# Adapter_-_Cabled_2_wire_CRXB4M.net
KiCad netlist of a schematic drawn in EAGLE
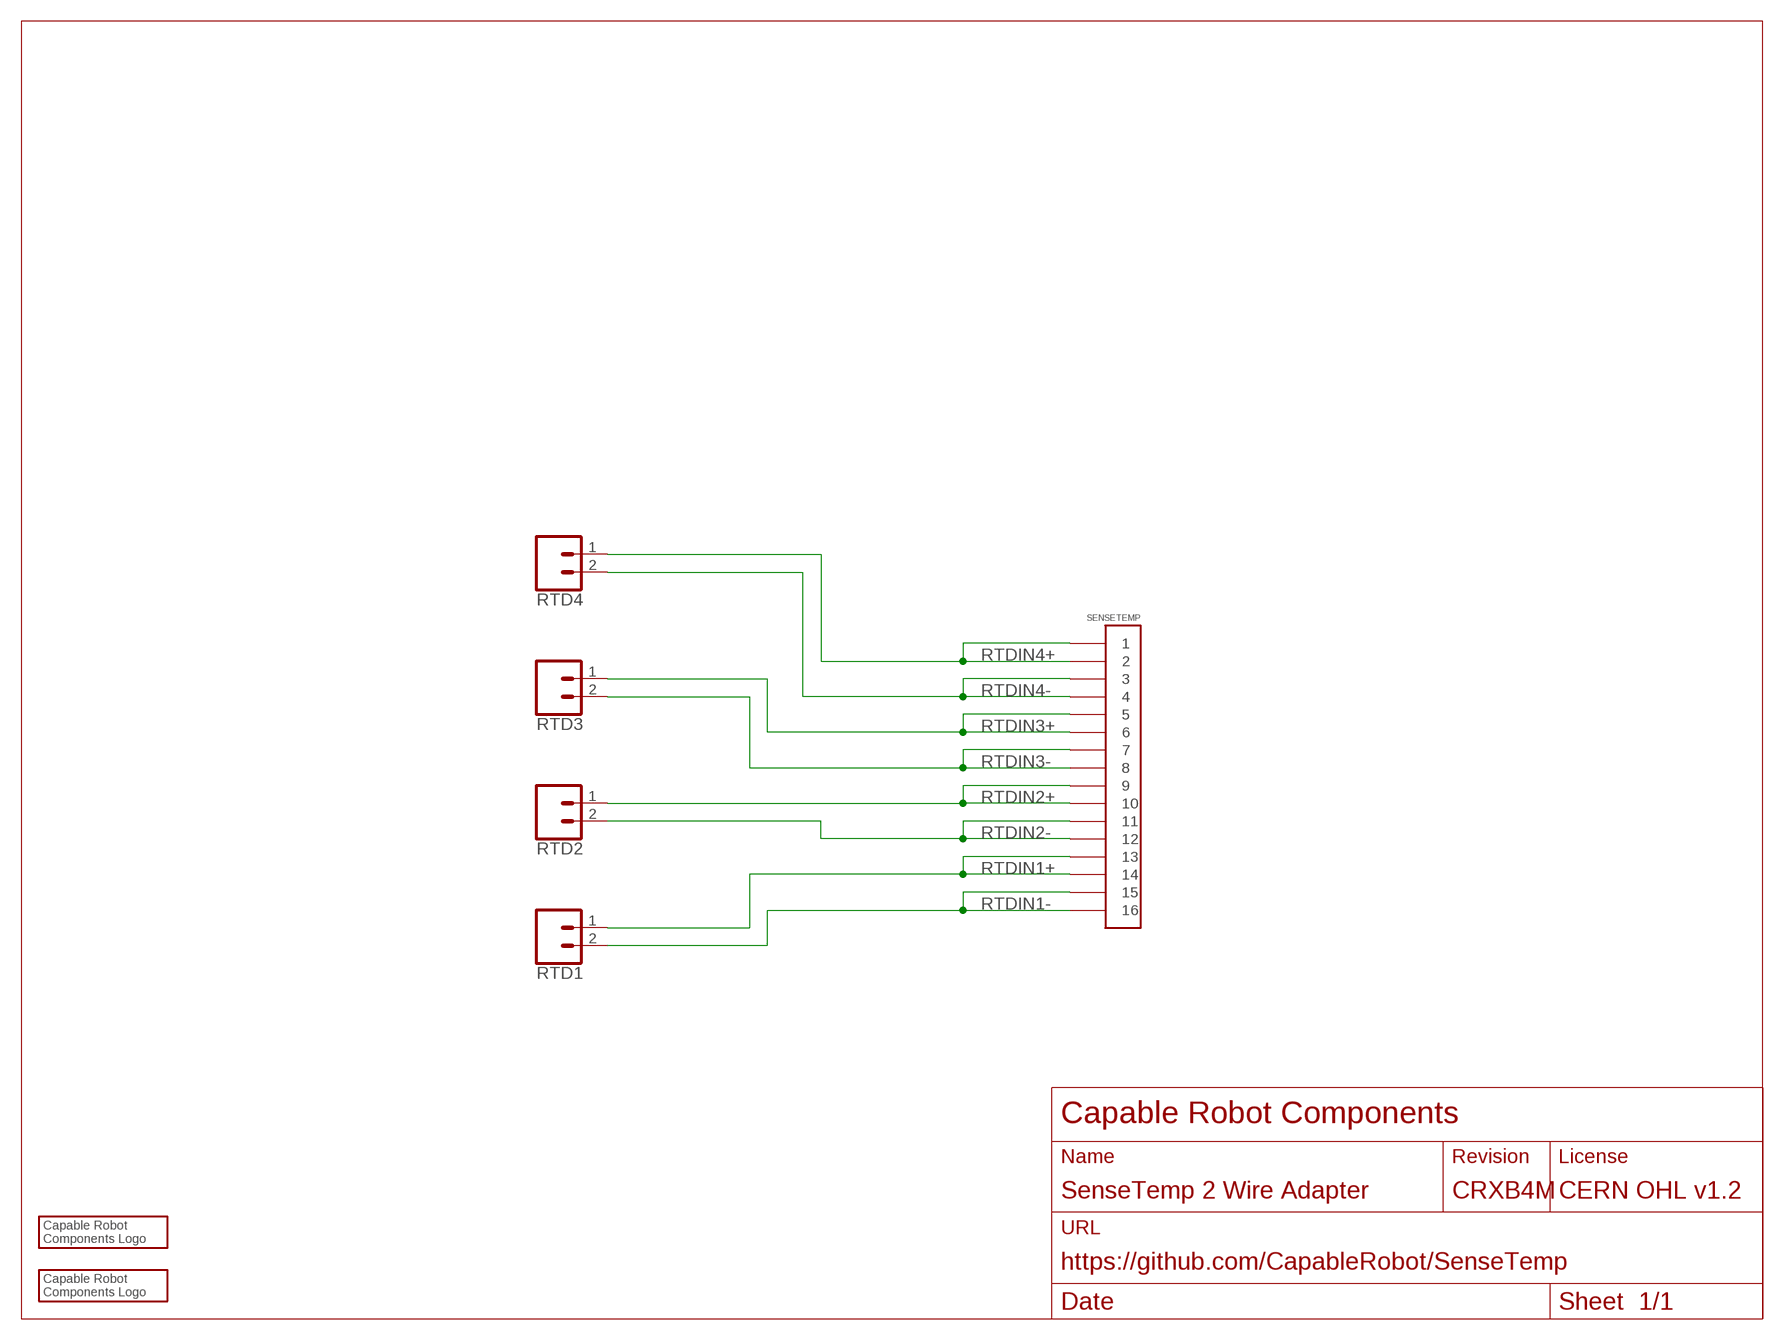
[diagram p0: schematic, sheet 1]

(export (version "E")
  (design (tool "Eeschema 10.0.6"))
  (components
    (comp (ref "LOGO1")
      (value "CRC-LOGO7SILK")
      (footprint "eagle-import:CRC-LOGO-7-SILK")
      (libsource (lib "eagle-import") (part "CRC-LOGO7SILK"))
    )
    (comp (ref "LOGO2")
      (value "CRC-LOGO5")
      (footprint "eagle-import:CRC-LOGO-5")
      (libsource (lib "eagle-import") (part "CRC-LOGO5"))
    )
    (comp (ref "RTD1")
      (value "CONN_025MM")
      (footprint "eagle-import:SCREWTERMINAL-5MM-2")
      (libsource (lib "eagle-import") (part "CONN_025MM"))
    )
    (comp (ref "RTD2")
      (value "CONN_025MM")
      (footprint "eagle-import:SCREWTERMINAL-5MM-2")
      (libsource (lib "eagle-import") (part "CONN_025MM"))
    )
    (comp (ref "RTD3")
      (value "CONN_025MM")
      (footprint "eagle-import:SCREWTERMINAL-5MM-2")
      (libsource (lib "eagle-import") (part "CONN_025MM"))
    )
    (comp (ref "RTD4")
      (value "CONN_025MM")
      (footprint "eagle-import:SCREWTERMINAL-5MM-2")
      (libsource (lib "eagle-import") (part "CONN_025MM"))
    )
    (comp (ref "SENSETEMP")
      (value "CONN-16ZT")
      (footprint "eagle-import:CONN-2X8-050-SMT-ZT")
      (fields (field (name "MPN") "3221-16-0300-00"))
      (libsource (lib "eagle-import") (part "CONN-16ZT"))
    )
  )
  (nets
    (net (code "1") (name "/RTDIN1+") (class "Default")
      (node (ref "RTD1") (pin "1") (pinfunction "1_1") (pintype "passive"))
      (node (ref "SENSETEMP") (pin "13") (pinfunction "13_13") (pintype "bidirectional"))
      (node (ref "SENSETEMP") (pin "14") (pinfunction "14_14") (pintype "bidirectional"))
    )
    (net (code "2") (name "/RTDIN1-") (class "Default")
      (node (ref "RTD1") (pin "2") (pinfunction "2_2") (pintype "passive"))
      (node (ref "SENSETEMP") (pin "15") (pinfunction "15_15") (pintype "bidirectional"))
      (node (ref "SENSETEMP") (pin "16") (pinfunction "16_16") (pintype "bidirectional"))
    )
    (net (code "3") (name "/RTDIN2+") (class "Default")
      (node (ref "RTD2") (pin "1") (pinfunction "1_1") (pintype "passive"))
      (node (ref "SENSETEMP") (pin "10") (pinfunction "10_10") (pintype "bidirectional"))
      (node (ref "SENSETEMP") (pin "9") (pinfunction "9_9") (pintype "bidirectional"))
    )
    (net (code "4") (name "/RTDIN2-") (class "Default")
      (node (ref "RTD2") (pin "2") (pinfunction "2_2") (pintype "passive"))
      (node (ref "SENSETEMP") (pin "11") (pinfunction "11_11") (pintype "bidirectional"))
      (node (ref "SENSETEMP") (pin "12") (pinfunction "12_12") (pintype "bidirectional"))
    )
    (net (code "5") (name "/RTDIN3+") (class "Default")
      (node (ref "RTD3") (pin "1") (pinfunction "1_1") (pintype "passive"))
      (node (ref "SENSETEMP") (pin "5") (pinfunction "5_5") (pintype "bidirectional"))
      (node (ref "SENSETEMP") (pin "6") (pinfunction "6_6") (pintype "bidirectional"))
    )
    (net (code "6") (name "/RTDIN3-") (class "Default")
      (node (ref "RTD3") (pin "2") (pinfunction "2_2") (pintype "passive"))
      (node (ref "SENSETEMP") (pin "7") (pinfunction "7_7") (pintype "bidirectional"))
      (node (ref "SENSETEMP") (pin "8") (pinfunction "8_8") (pintype "bidirectional"))
    )
    (net (code "7") (name "/RTDIN4+") (class "Default")
      (node (ref "RTD4") (pin "1") (pinfunction "1_1") (pintype "passive"))
      (node (ref "SENSETEMP") (pin "1") (pinfunction "1_1") (pintype "bidirectional"))
      (node (ref "SENSETEMP") (pin "2") (pinfunction "2_2") (pintype "bidirectional"))
    )
    (net (code "8") (name "/RTDIN4-") (class "Default")
      (node (ref "RTD4") (pin "2") (pinfunction "2_2") (pintype "passive"))
      (node (ref "SENSETEMP") (pin "3") (pinfunction "3_3") (pintype "bidirectional"))
      (node (ref "SENSETEMP") (pin "4") (pinfunction "4_4") (pintype "bidirectional"))
    )
  )
)
